# CAN_Interface.net
KiCad netlist of a schematic drawn in Altium Designer
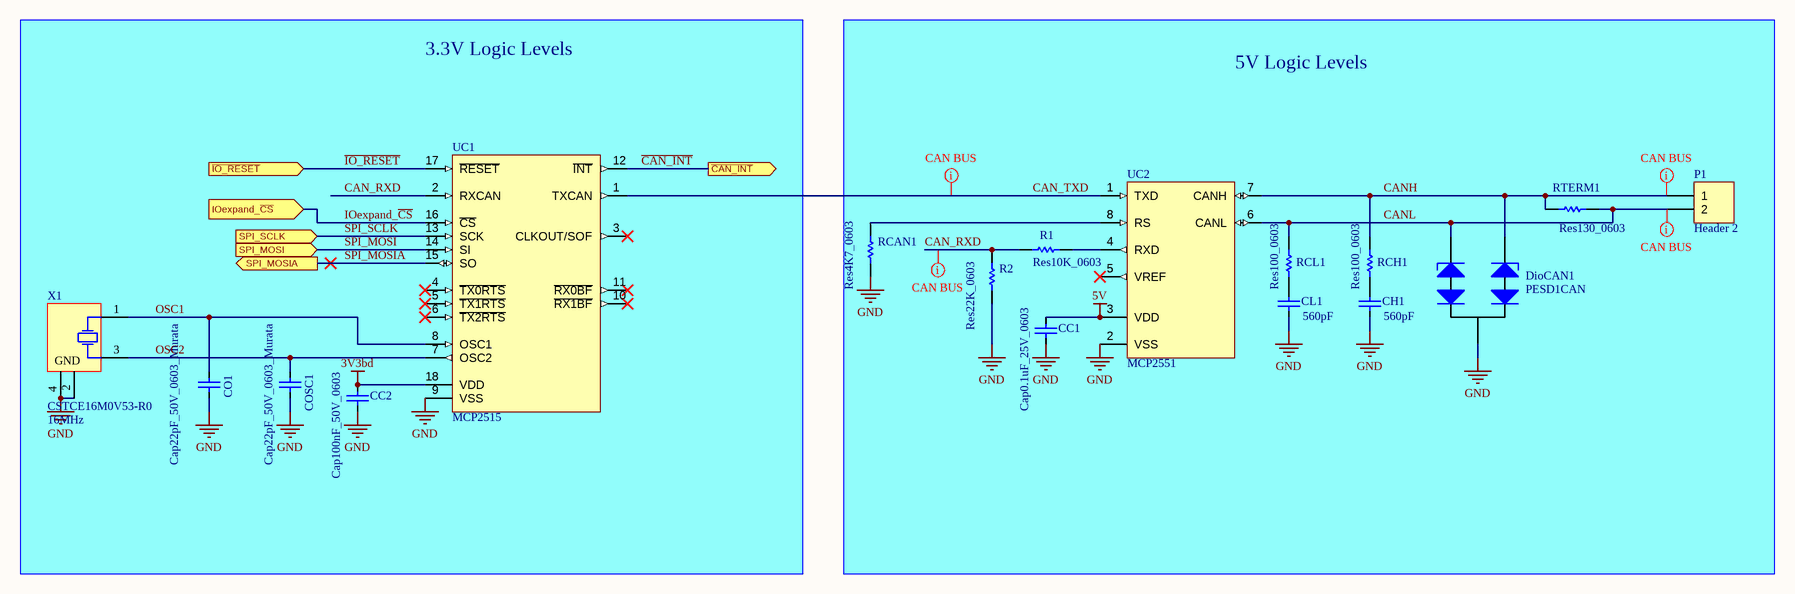
[diagram p0:  CAN_Interface.SchDoc]

(export (version "E")
  (design (tool "Eeschema 10.0.6"))
  (components
    (comp (ref "CC1")
      (value "Cap0.1uF_25V_0603")
      (footprint "0603C_L")
      (libsource (lib " Advanced] Training Course - A365") (part "CAP General"))
    )
    (comp (ref "CC2")
      (value "Cap100nF_50V_0603")
      (footprint "0603C_L")
      (libsource (lib " Advanced] Training Course - A365") (part "CAP General"))
    )
    (comp (ref "CH1")
      (value "560pF")
      (footprint "0603C_L")
      (description "560pF 25V 0603")
      (fields (field (name "Comment") "CAP General"))
      (libsource (lib " Advanced] Training Course - A365") (part "CAP General"))
    )
    (comp (ref "CL1")
      (value "560pF")
      (footprint "0603C_L")
      (description "560pF 25V 0603")
      (fields (field (name "Comment") "CAP General"))
      (libsource (lib " Advanced] Training Course - A365") (part "CAP General"))
    )
    (comp (ref "CO1")
      (value "Cap22pF_50V_0603_Murata")
      (footprint "0603C_L")
      (fields (field (name "TOLERANCE") "5%"))
      (libsource (lib " Advanced] Training Course - A365") (part "CAP General"))
    )
    (comp (ref "COSC1")
      (value "Cap22pF_50V_0603_Murata")
      (footprint "0603C_L")
      (fields (field (name "TOLERANCE") "5%"))
      (libsource (lib " Advanced] Training Course - A365") (part "CAP General"))
    )
    (comp (ref "DioCAN1")
      (value "PESD1CAN")
      (footprint "SOT323")
      (description "Trans Voltage Suppressor Diode, 150W, 24V V(RWM), Bidirectional, 2 Element, Silicon")
      (fields (field (name "MANUFACTURER") "Nexperia USA Inc.") (field (name "SOURCE") "WCT.SchLib"))
      (libsource (lib " Advanced] Training Course - A365") (part "PESD1CAN"))
    )
    (comp (ref "P1")
      (value "Header 2")
      (footprint "HDR1X2")
      (description "Header, 2-Pin")
      (fields (field (name "PUBLISHER") "Altium Limited") (field (name "SOURCE") "WCT.SchLib"))
      (libsource (lib " Advanced] Training Course - A365") (part "Header 2"))
    )
    (comp (ref "R1")
      (value "Res10K_0603")
      (footprint "0603_L")
      (fields
        (field (name "MANUFACTURER") "Panasonic Electronic Components")
        (field (name "MANUFACTURER PART NUMBER") "ERJ-3GEYJ102V")
        (field (name "TOLERANCE") "5%")
        (field (name "SOURCE") "WCT.SchLib")
      )
      (libsource (lib " Advanced] Training Course - A365") (part "Resistor General"))
    )
    (comp (ref "R2")
      (value "Res22K_0603")
      (footprint "0603_L")
      (description "RES22K 0.5% 0603")
      (fields
        (field (name "MANUFACTURER") "Yageo")
        (field (name "MANUFACTURER PART NUMBER") "RT0603DRD0722KL")
        (field (name "SOURCE") "WCT.SchLib")
      )
      (libsource (lib " Advanced] Training Course - A365") (part "Resistor General"))
    )
    (comp (ref "RCAN1")
      (value "Res4K7_0603")
      (footprint "0603_L")
      (fields
        (field (name "MANUFACTURER") "Yageo")
        (field (name "TOLERANCE") "0.5%")
        (field (name "SOURCE") "WCT.SchLib")
      )
      (libsource (lib " Advanced] Training Course - A365") (part "Resistor General"))
    )
    (comp (ref "RCH1")
      (value "Res100_0603")
      (footprint "0603_L")
      (fields
        (field (name "MANUFACTURER") "Panasonic Electronic Components")
        (field (name "TOLERANCE") "5%")
        (field (name "SOURCE") "WCT.SchLib")
      )
      (libsource (lib " Advanced] Training Course - A365") (part "Resistor General"))
    )
    (comp (ref "RCL1")
      (value "Res100_0603")
      (footprint "0603_L")
      (fields
        (field (name "MANUFACTURER") "Panasonic Electronic Components")
        (field (name "TOLERANCE") "5%")
        (field (name "SOURCE") "WCT.SchLib")
      )
      (libsource (lib " Advanced] Training Course - A365") (part "Resistor General"))
    )
    (comp (ref "RTERM1")
      (value "Res130_0603")
      (footprint "0603_L")
      (fields
        (field (name "MANUFACTURER") "Panasonic Electronic Components")
        (field (name "TOLERANCE") "5%")
        (field (name "SOURCE") "WCT.SchLib")
      )
      (libsource (lib " Advanced] Training Course - A365") (part "Resistor General"))
    )
    (comp (ref "UC1")
      (value "MCP2515")
      (footprint "SOIC-SO18_M")
      (description "Stand-Alone CAN Controller With SPI Interface, 18-Pin SOIC, Extended Temperature")
      (fields
        (field (name "MANUFACTURER") "Microchip")
        (field (name "MANUFACTURER PART NUMBER") "MCP2515-E/SO")
        (field (name "AVAILABLE PREVIEW IMAGES") "2D")
        (field (name "SOURCE") "WCT.SchLib")
      )
      (libsource (lib " Advanced] Training Course - A365") (part "MCP2515"))
    )
    (comp (ref "UC2")
      (value "MCP2551")
      (footprint "SOIC-SN8_N")
      (description "High-Speed CAN Transceiver, 8-Pin SOIC, Extended Temperature")
      (fields
        (field (name "MANUFACTURER") "Microchip")
        (field (name "MANUFACTURER PART NUMBER") "MCP2551-E/SN")
        (field (name "AVAILABLE PREVIEW IMAGES") "2D")
        (field (name "SOURCE") "WCT.SchLib")
      )
      (libsource (lib " Advanced] Training Course - A365") (part "MCP2551"))
    )
    (comp (ref "X1")
      (value "CSTCE16M0V53-R0")
      (footprint "FP-ABM8-MFG")
      (description "Crystal 16MHz ±20ppm 18pF SMD-4 3.2mm x 2.5mm CSTCE16M0V53-R0 ABM8-16.000MHZ-B2-T")
      (fields
        (field (name "TOLERANCE") "20ppm")
        (field (name "FREQUENCY") "16MHz")
        (field (name "SOURCE") "WCT.SchLib")
      )
      (libsource (lib " Advanced] Training Course - A365") (part "Crystal 4Pin"))
    )
  )
  (nets
    (net (code "1") (name "/CANH") (class "Default")
      (node (ref "DioCAN1") (pin "1") (pinfunction "A_1") (pintype "passive"))
      (node (ref "P1") (pin "1") (pinfunction "1_1") (pintype "passive"))
      (node (ref "RCH1") (pin "2") (pinfunction "2_2") (pintype "passive"))
      (node (ref "RTERM1") (pin "2") (pinfunction "2_2") (pintype "passive"))
      (node (ref "UC2") (pin "7") (pinfunction "CANH_7") (pintype "bidirectional"))
    )
    (net (code "2") (name "/CANL") (class "Default")
      (node (ref "DioCAN1") (pin "2") (pinfunction "K_2") (pintype "passive"))
      (node (ref "P1") (pin "2") (pinfunction "2_2") (pintype "passive"))
      (node (ref "RCL1") (pin "2") (pinfunction "2_2") (pintype "passive"))
      (node (ref "RTERM1") (pin "1") (pinfunction "1_1") (pintype "passive"))
      (node (ref "UC2") (pin "6") (pinfunction "CANL_6") (pintype "bidirectional"))
    )
    (net (code "3") (name "/CAN_INT") (class "Default")
      (node (ref "UC1") (pin "12") (pinfunction "~{INT}_12") (pintype "output"))
    )
    (net (code "4") (name "/CAN_RXD") (class "Default")
      (node (ref "R1") (pin "2") (pinfunction "2_2") (pintype "passive"))
      (node (ref "R2") (pin "2") (pinfunction "2_2") (pintype "passive"))
      (node (ref "UC1") (pin "2") (pinfunction "RXCAN_2") (pintype "input"))
    )
    (net (code "5") (name "/CAN_TXD") (class "Default")
      (node (ref "UC1") (pin "1") (pinfunction "TXCAN_1") (pintype "output"))
      (node (ref "UC2") (pin "1") (pinfunction "TXD_1") (pintype "input"))
    )
    (net (code "6") (name "/IO_RESET") (class "Default")
      (node (ref "UC1") (pin "17") (pinfunction "~{RESET}_17") (pintype "input"))
    )
    (net (code "7") (name "/IOexpand_~{CS}") (class "Default")
      (node (ref "UC1") (pin "16") (pinfunction "~{CS}_16") (pintype "input"))
    )
    (net (code "8") (name "/OSC1") (class "Default")
      (node (ref "CO1") (pin "2") (pinfunction "2_2") (pintype "passive"))
      (node (ref "UC1") (pin "8") (pinfunction "OSC1_8") (pintype "input"))
      (node (ref "X1") (pin "1") (pinfunction "1_1") (pintype "passive"))
    )
    (net (code "9") (name "/OSC2") (class "Default")
      (node (ref "COSC1") (pin "2") (pinfunction "2_2") (pintype "passive"))
      (node (ref "UC1") (pin "7") (pinfunction "OSC2_7") (pintype "output"))
      (node (ref "X1") (pin "3") (pinfunction "3_3") (pintype "passive"))
    )
    (net (code "10") (name "/SPI_MOSI") (class "Default")
      (node (ref "UC1") (pin "14") (pinfunction "SI_14") (pintype "input"))
    )
    (net (code "11") (name "/SPI_MOSIA") (class "Default")
      (node (ref "UC1") (pin "15") (pinfunction "SO_15") (pintype "bidirectional"))
    )
    (net (code "12") (name "/SPI_SCLK") (class "Default")
      (node (ref "UC1") (pin "13") (pinfunction "SCK_13") (pintype "input"))
    )
    (net (code "13") (name "3V3bd") (class "Default")
      (node (ref "CC2") (pin "2") (pinfunction "2_2") (pintype "passive"))
      (node (ref "UC1") (pin "18") (pinfunction "VDD_18") (pintype "power_in"))
    )
    (net (code "14") (name "5V") (class "Default")
      (node (ref "CC1") (pin "2") (pinfunction "2_2") (pintype "passive"))
      (node (ref "UC2") (pin "3") (pinfunction "VDD_3") (pintype "power_in"))
    )
    (net (code "15") (name "GND") (class "Default")
      (node (ref "CC1") (pin "1") (pinfunction "1_1") (pintype "passive"))
      (node (ref "CC2") (pin "1") (pinfunction "1_1") (pintype "passive"))
      (node (ref "CH1") (pin "2") (pinfunction "2_2") (pintype "passive"))
      (node (ref "CL1") (pin "1") (pinfunction "1_1") (pintype "passive"))
      (node (ref "CO1") (pin "1") (pinfunction "1_1") (pintype "passive"))
      (node (ref "COSC1") (pin "1") (pinfunction "1_1") (pintype "passive"))
      (node (ref "DioCAN1") (pin "3") (pinfunction "3_3") (pintype "passive"))
      (node (ref "R2") (pin "1") (pinfunction "1_1") (pintype "passive"))
      (node (ref "RCAN1") (pin "1") (pinfunction "1_1") (pintype "passive"))
      (node (ref "UC1") (pin "9") (pinfunction "VSS_9") (pintype "power_in"))
      (node (ref "UC2") (pin "2") (pinfunction "VSS_2") (pintype "power_in"))
      (node (ref "X1") (pin "2") (pinfunction "GND_2") (pintype "power_in"))
      (node (ref "X1") (pin "4") (pinfunction "GND_4") (pintype "power_in"))
    )
    (net (code "16") (name "Net-(CH1-Pad1)") (class "Default")
      (node (ref "CH1") (pin "1") (pinfunction "1_1") (pintype "passive"))
      (node (ref "RCH1") (pin "1") (pinfunction "1_1") (pintype "passive"))
    )
    (net (code "17") (name "Net-(CL1-Pad2)") (class "Default")
      (node (ref "CL1") (pin "2") (pinfunction "2_2") (pintype "passive"))
      (node (ref "RCL1") (pin "1") (pinfunction "1_1") (pintype "passive"))
    )
    (net (code "18") (name "Net-(UC2-RS)") (class "Default")
      (node (ref "RCAN1") (pin "2") (pinfunction "2_2") (pintype "passive"))
      (node (ref "UC2") (pin "8") (pinfunction "RS_8") (pintype "input"))
    )
    (net (code "19") (name "Net-(UC2-RXD)") (class "Default")
      (node (ref "R1") (pin "1") (pinfunction "1_1") (pintype "passive"))
      (node (ref "UC2") (pin "4") (pinfunction "RXD_4") (pintype "output"))
    )
    (net (code "20") (name "unconnected-(UC1-CLKOUT{slash}SOF-Pad3)") (class "Default")
      (node (ref "UC1") (pin "3") (pinfunction "CLKOUT/SOF_3") (pintype "output+no_connect"))
    )
    (net (code "21") (name "unconnected-(UC1-~{RX0BF}-Pad11)") (class "Default")
      (node (ref "UC1") (pin "11") (pinfunction "~{RX0BF}_11") (pintype "output+no_connect"))
    )
    (net (code "22") (name "unconnected-(UC1-~{RX1BF}-Pad10)") (class "Default")
      (node (ref "UC1") (pin "10") (pinfunction "~{RX1BF}_10") (pintype "output+no_connect"))
    )
    (net (code "23") (name "unconnected-(UC1-~{TX0RTS}-Pad4)") (class "Default")
      (node (ref "UC1") (pin "4") (pinfunction "~{TX0RTS}_4") (pintype "input+no_connect"))
    )
    (net (code "24") (name "unconnected-(UC1-~{TX1RTS}-Pad5)") (class "Default")
      (node (ref "UC1") (pin "5") (pinfunction "~{TX1RTS}_5") (pintype "input+no_connect"))
    )
    (net (code "25") (name "unconnected-(UC1-~{TX2RTS}-Pad6)") (class "Default")
      (node (ref "UC1") (pin "6") (pinfunction "~{TX2RTS}_6") (pintype "input+no_connect"))
    )
    (net (code "26") (name "unconnected-(UC2-VREF-Pad5)") (class "Default")
      (node (ref "UC2") (pin "5") (pinfunction "VREF_5") (pintype "output+no_connect"))
    )
  )
)
